# DAAD_DIMER_Sheet.net
KiCad netlist of a schematic drawn in Altium Designer
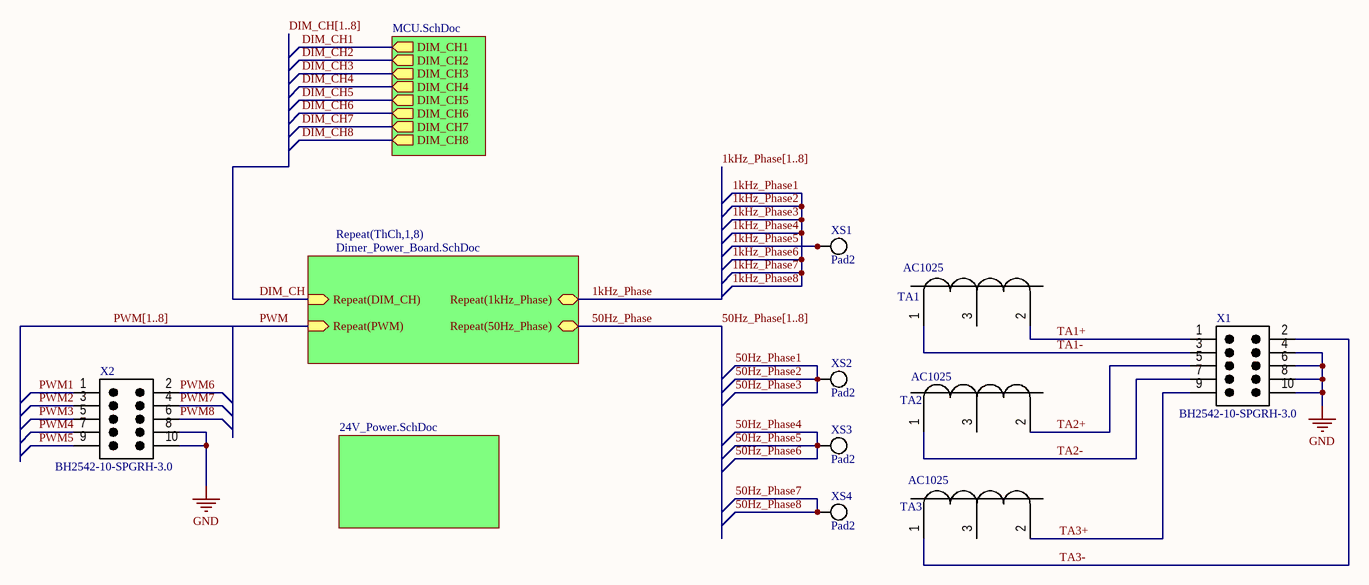
[diagram p0: DAAD_DIMER_Sheet.SchDoc]

(export (version "E")
  (design (tool "Eeschema 10.0.6"))
  (components
    (comp (ref "TA1")
      (value "AC1025")
      (footprint "10K_TRIM")
      (description "Talema India Current Trancducer 45/15 AC1025")
      (libsource (lib "Nolden_Power_Board_V2") (part "Talema 45/15 AC1025"))
    )
    (comp (ref "TA2")
      (value "AC1025")
      (footprint "10K_TRIM")
      (description "Talema India Current Trancducer 45/15 AC1025")
      (libsource (lib "Nolden_Power_Board_V2") (part "Talema 45/15 AC1025"))
    )
    (comp (ref "TA3")
      (value "AC1025")
      (footprint "10K_TRIM")
      (description "Talema India Current Trancducer 45/15 AC1025")
      (libsource (lib "Nolden_Power_Board_V2") (part "Talema 45/15 AC1025"))
    )
    (comp (ref "X1")
      (value "BH2542-10-SPGRH-3.0")
      (footprint "PCE-BH2542-10-SPGRH-3.0")
      (description "Box Header, Pitch 2.54 mm, 2x5 Position, Height 9 mm, Tail Length 3 mm")
      (fields (field (name "MANUFACTURER") "Pinchao Electronic"))
      (libsource (lib "Nolden_Power_Board_V2") (part "PCE-HDR-2P-M-R10"))
    )
    (comp (ref "X2")
      (value "BH2542-10-SPGRH-3.0")
      (footprint "PCE-BH2542-10-SPGRH-3.0")
      (description "Box Header, Pitch 2.54 mm, 2x5 Position, Height 9 mm, Tail Length 3 mm")
      (fields (field (name "MANUFACTURER") "Pinchao Electronic"))
      (libsource (lib "Nolden_Power_Board_V2") (part "PCE-HDR-2P-M-R10"))
    )
    (comp (ref "XS1")
      (value "Pad2")
      (footprint "LOTPAD_2")
      (description "PCB TH Pad")
      (libsource (lib "Nolden_Power_Board_V2") (part "Pad2"))
    )
    (comp (ref "XS2")
      (value "Pad2")
      (footprint "LOTPAD_2")
      (description "PCB TH Pad")
      (libsource (lib "Nolden_Power_Board_V2") (part "Pad2"))
    )
    (comp (ref "XS3")
      (value "Pad2")
      (footprint "LOTPAD_2")
      (description "PCB TH Pad")
      (libsource (lib "Nolden_Power_Board_V2") (part "Pad2"))
    )
    (comp (ref "XS4")
      (value "Pad2")
      (footprint "LOTPAD_2")
      (description "PCB TH Pad")
      (libsource (lib "Nolden_Power_Board_V2") (part "Pad2"))
    )
  )
  (nets
    (net (code "2") (name "/1kHz_Phase5") (class "Default")
      (node (ref "XS1") (pin "1") (pinfunction "1_1") (pintype "passive"))
      (node (ref "XS1") (pin "2") (pinfunction "2_2") (pintype "passive"))
    )
    (net (code "6") (name "/50Hz_Phase3") (class "Default")
      (node (ref "XS2") (pin "1") (pinfunction "1_1") (pintype "passive"))
      (node (ref "XS2") (pin "2") (pinfunction "2_2") (pintype "passive"))
    )
    (net (code "7") (name "/50Hz_Phase6") (class "Default")
      (node (ref "XS3") (pin "1") (pinfunction "1_1") (pintype "passive"))
      (node (ref "XS3") (pin "2") (pinfunction "2_2") (pintype "passive"))
    )
    (net (code "8") (name "/50Hz_Phase8") (class "Default")
      (node (ref "XS4") (pin "1") (pinfunction "1_1") (pintype "passive"))
      (node (ref "XS4") (pin "2") (pinfunction "2_2") (pintype "passive"))
    )
    (net (code "21") (name "/PWM1") (class "Default")
      (node (ref "X2") (pin "1") (pinfunction "1_1") (pintype "passive"))
    )
    (net (code "22") (name "/PWM2") (class "Default")
      (node (ref "X2") (pin "3") (pinfunction "3_3") (pintype "passive"))
    )
    (net (code "23") (name "/PWM3") (class "Default")
      (node (ref "X2") (pin "5") (pinfunction "5_5") (pintype "passive"))
    )
    (net (code "24") (name "/PWM4") (class "Default")
      (node (ref "X2") (pin "7") (pinfunction "7_7") (pintype "passive"))
    )
    (net (code "25") (name "/PWM5") (class "Default")
      (node (ref "X2") (pin "9") (pinfunction "9_9") (pintype "passive"))
    )
    (net (code "26") (name "/PWM6") (class "Default")
      (node (ref "X2") (pin "2") (pinfunction "2_2") (pintype "passive"))
    )
    (net (code "27") (name "/PWM7") (class "Default")
      (node (ref "X2") (pin "4") (pinfunction "4_4") (pintype "passive"))
    )
    (net (code "28") (name "/PWM8") (class "Default")
      (node (ref "X2") (pin "6") (pinfunction "6_6") (pintype "passive"))
    )
    (net (code "30") (name "/TA1+") (class "Default")
      (node (ref "TA1") (pin "2") (pinfunction "2_2") (pintype "passive"))
      (node (ref "X1") (pin "1") (pinfunction "1_1") (pintype "passive"))
    )
    (net (code "31") (name "/TA1-") (class "Default")
      (node (ref "TA1") (pin "1") (pinfunction "1_1") (pintype "passive"))
      (node (ref "X1") (pin "3") (pinfunction "3_3") (pintype "passive"))
    )
    (net (code "32") (name "/TA2+") (class "Default")
      (node (ref "TA2") (pin "2") (pinfunction "2_2") (pintype "passive"))
      (node (ref "X1") (pin "5") (pinfunction "5_5") (pintype "passive"))
    )
    (net (code "33") (name "/TA2-") (class "Default")
      (node (ref "TA2") (pin "1") (pinfunction "1_1") (pintype "passive"))
      (node (ref "X1") (pin "7") (pinfunction "7_7") (pintype "passive"))
    )
    (net (code "34") (name "/TA3+") (class "Default")
      (node (ref "TA3") (pin "2") (pinfunction "2_2") (pintype "passive"))
      (node (ref "X1") (pin "9") (pinfunction "9_9") (pintype "passive"))
    )
    (net (code "35") (name "/TA3-") (class "Default")
      (node (ref "TA3") (pin "1") (pinfunction "1_1") (pintype "passive"))
      (node (ref "X1") (pin "2") (pinfunction "2_2") (pintype "passive"))
    )
    (net (code "36") (name "GND") (class "Default")
      (node (ref "X1") (pin "10") (pinfunction "10_10") (pintype "passive"))
      (node (ref "X1") (pin "4") (pinfunction "4_4") (pintype "passive"))
      (node (ref "X1") (pin "6") (pinfunction "6_6") (pintype "passive"))
      (node (ref "X1") (pin "8") (pinfunction "8_8") (pintype "passive"))
      (node (ref "X2") (pin "10") (pinfunction "10_10") (pintype "passive"))
      (node (ref "X2") (pin "8") (pinfunction "8_8") (pintype "passive"))
    )
    (net (code "37") (name "unconnected-(TA1-Pad3)") (class "Default")
      (node (ref "TA1") (pin "3") (pinfunction "3_3") (pintype "passive"))
    )
    (net (code "38") (name "unconnected-(TA2-Pad3)") (class "Default")
      (node (ref "TA2") (pin "3") (pinfunction "3_3") (pintype "passive"))
    )
    (net (code "39") (name "unconnected-(TA3-Pad3)") (class "Default")
      (node (ref "TA3") (pin "3") (pinfunction "3_3") (pintype "passive"))
    )
  )
)
